# Sensor-HDC1008.net
KiCad netlist of a schematic drawn in EAGLE
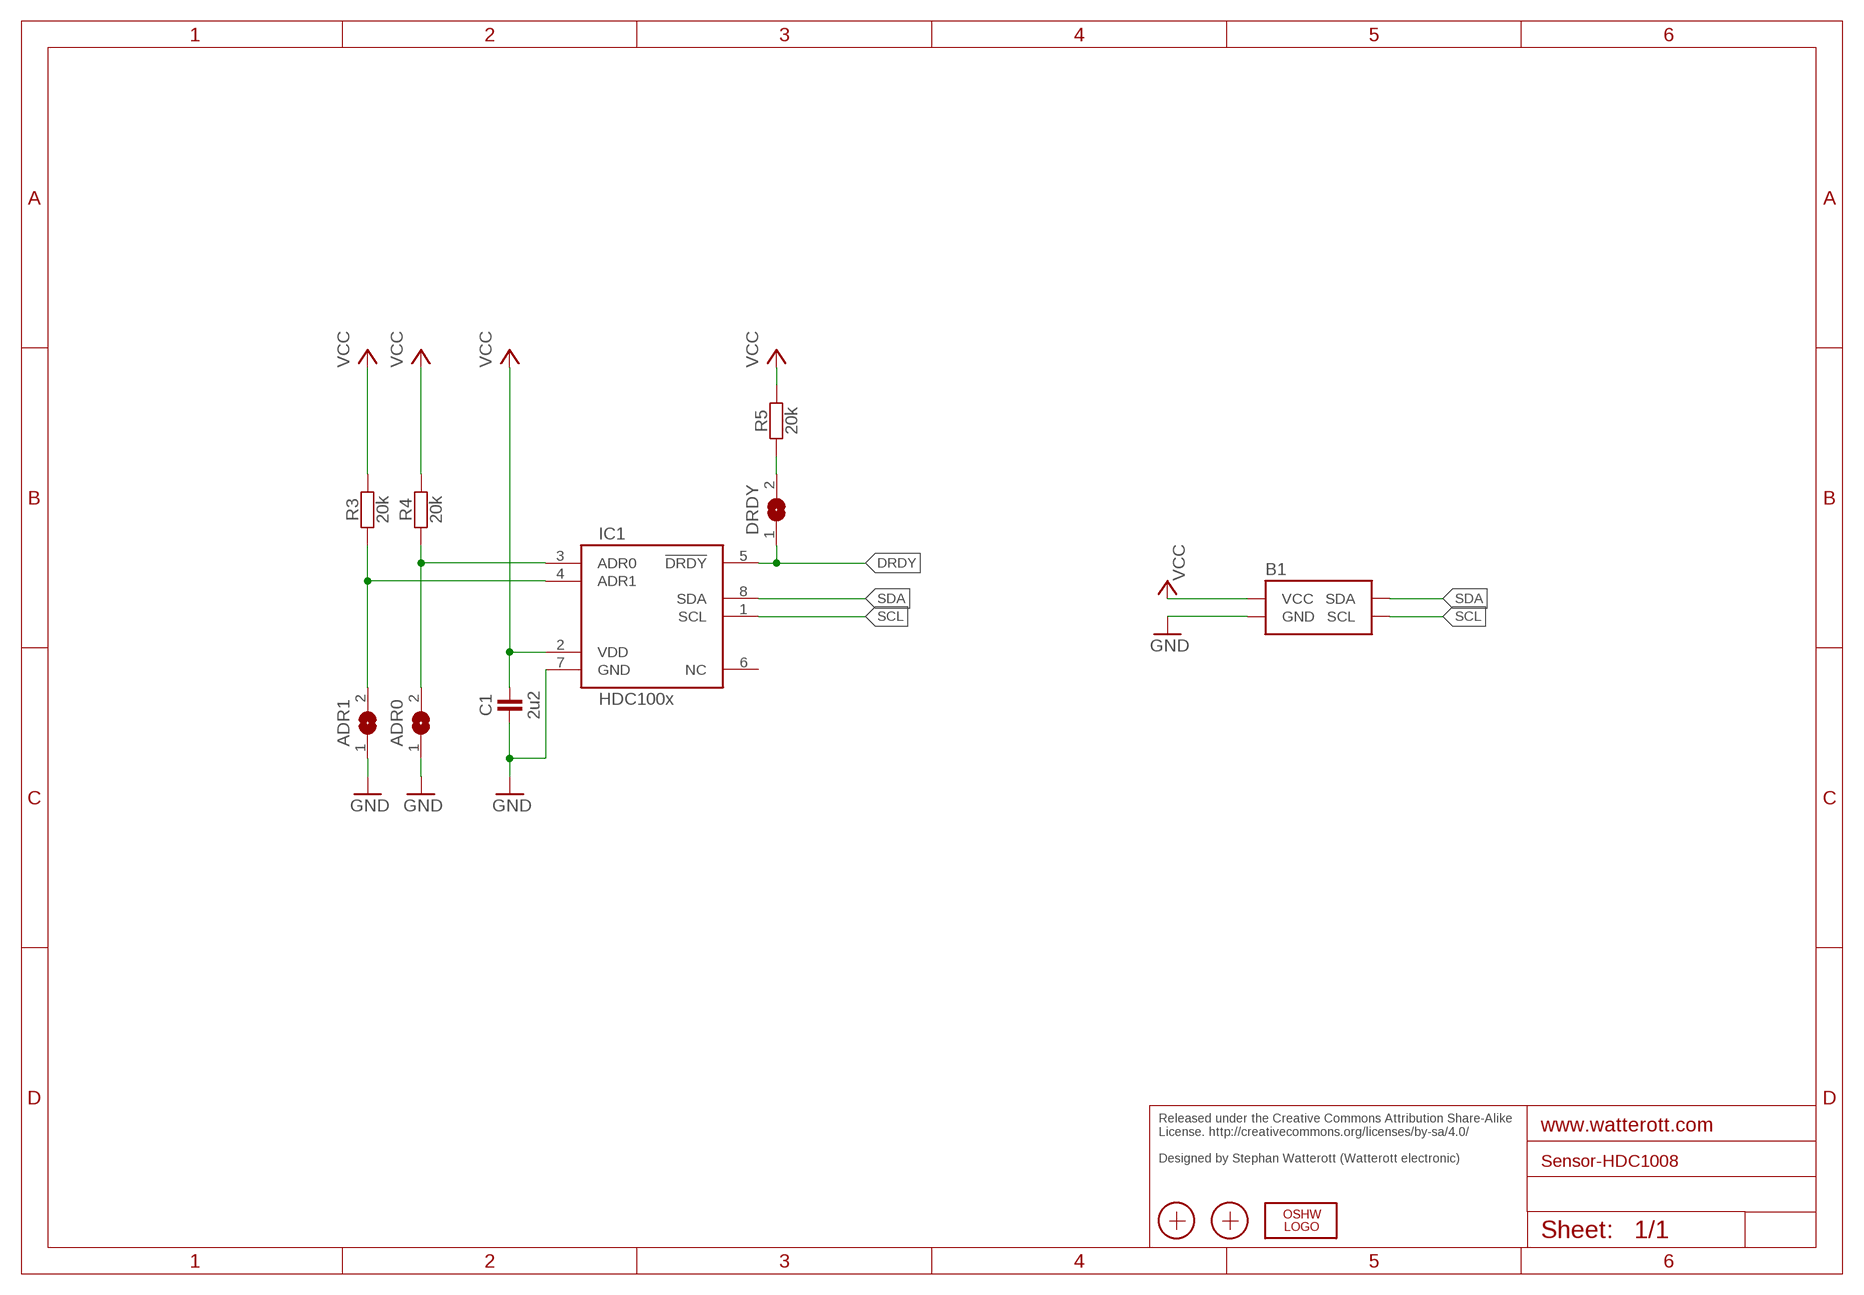
[diagram p0: schematic, sheet 1]

(export (version "E")
  (design (tool "Eeschema 10.0.6"))
  (components
    (comp (ref "ADR0")
      (value "JUMPER2-0402")
      (footprint "eagle-import:JUMPER2-0402")
      (libsource (lib "eagle-import") (part "JUMPER2-0402"))
    )
    (comp (ref "ADR1")
      (value "JUMPER2-0402")
      (footprint "eagle-import:JUMPER2-0402")
      (libsource (lib "eagle-import") (part "JUMPER2-0402"))
    )
    (comp (ref "B1")
      (value "SENSEBOX_I2C")
      (footprint "eagle-import:SENSEBOX_I2C")
      (libsource (lib "eagle-import") (part "SENSEBOX_I2C"))
    )
    (comp (ref "C1")
      (value "2u2")
      (footprint "eagle-import:R0402")
      (libsource (lib "eagle-import") (part "CAPACITOR-C0402"))
    )
    (comp (ref "DRDY")
      (value "JUMPER2-0402")
      (footprint "eagle-import:JUMPER2-0402")
      (libsource (lib "eagle-import") (part "JUMPER2-0402"))
    )
    (comp (ref "IC1")
      (value "HDC100x")
      (footprint "eagle-import:WLCSP")
      (libsource (lib "eagle-import") (part "HDC1008"))
    )
    (comp (ref "LOGO2")
      (value "OSHW_LOGOX0070")
      (footprint "eagle-import:OSHW_6X70")
      (libsource (lib "eagle-import") (part "OSHW_LOGOX0070"))
    )
    (comp (ref "R3")
      (value "20k")
      (footprint "eagle-import:R0402")
      (libsource (lib "eagle-import") (part "RESISTOR-R0402"))
    )
    (comp (ref "R4")
      (value "20k")
      (footprint "eagle-import:R0402")
      (libsource (lib "eagle-import") (part "RESISTOR-R0402"))
    )
    (comp (ref "R5")
      (value "20k")
      (footprint "eagle-import:R0402")
      (libsource (lib "eagle-import") (part "RESISTOR-R0402"))
    )
    (comp (ref "X1")
      (value "PASSER-07")
      (footprint "eagle-import:PASSER_07MM")
      (libsource (lib "eagle-import") (part "PASSER-07"))
    )
    (comp (ref "X2")
      (value "PASSER-07")
      (footprint "eagle-import:PASSER_07MM")
      (libsource (lib "eagle-import") (part "PASSER-07"))
    )
  )
  (nets
    (net (code "1") (name "DRDY") (class "Default")
      (node (ref "DRDY") (pin "1") (pinfunction "1_1") (pintype "passive"))
      (node (ref "IC1") (pin "5") (pinfunction "~{DRDY}_5") (pintype "output"))
    )
    (net (code "2") (name "GND") (class "Default")
      (node (ref "ADR0") (pin "1") (pinfunction "1_1") (pintype "passive"))
      (node (ref "ADR1") (pin "1") (pinfunction "1_1") (pintype "passive"))
      (node (ref "B1") (pin "GND") (pinfunction "GND_GND") (pintype "power_in"))
      (node (ref "C1") (pin "1") (pinfunction "1_1") (pintype "passive"))
      (node (ref "IC1") (pin "7") (pinfunction "GND_7") (pintype "power_in"))
    )
    (net (code "3") (name "Net-(DRDY-Pad2)") (class "Default")
      (node (ref "DRDY") (pin "2") (pinfunction "2_2") (pintype "passive"))
      (node (ref "R5") (pin "1") (pinfunction "1_1") (pintype "passive"))
    )
    (net (code "4") (name "Net-(IC1-ADR0)") (class "Default")
      (node (ref "ADR0") (pin "2") (pinfunction "2_2") (pintype "passive"))
      (node (ref "IC1") (pin "3") (pinfunction "ADR0_3") (pintype "input"))
      (node (ref "R4") (pin "1") (pinfunction "1_1") (pintype "passive"))
    )
    (net (code "5") (name "Net-(IC1-ADR1)") (class "Default")
      (node (ref "ADR1") (pin "2") (pinfunction "2_2") (pintype "passive"))
      (node (ref "IC1") (pin "4") (pinfunction "ADR1_4") (pintype "input"))
      (node (ref "R3") (pin "1") (pinfunction "1_1") (pintype "passive"))
    )
    (net (code "6") (name "SCL") (class "Default")
      (node (ref "B1") (pin "SCL") (pinfunction "SCL_SCL") (pintype "bidirectional"))
      (node (ref "IC1") (pin "1") (pinfunction "SCL_1") (pintype "input"))
    )
    (net (code "7") (name "SDA") (class "Default")
      (node (ref "B1") (pin "SDA") (pinfunction "SDA_SDA") (pintype "bidirectional"))
      (node (ref "IC1") (pin "8") (pinfunction "SDA_8") (pintype "bidirectional"))
    )
    (net (code "8") (name "VCC") (class "Default")
      (node (ref "B1") (pin "VCC") (pinfunction "VCC_VCC") (pintype "power_in"))
      (node (ref "C1") (pin "2") (pinfunction "2_2") (pintype "passive"))
      (node (ref "IC1") (pin "2") (pinfunction "VDD_2") (pintype "power_in"))
      (node (ref "R3") (pin "2") (pinfunction "2_2") (pintype "passive"))
      (node (ref "R4") (pin "2") (pinfunction "2_2") (pintype "passive"))
      (node (ref "R5") (pin "2") (pinfunction "2_2") (pintype "passive"))
    )
    (net (code "9") (name "unconnected-(IC1-NC-Pad6)") (class "Default")
      (node (ref "IC1") (pin "6") (pinfunction "NC_6") (pintype "no_connect"))
    )
  )
)
